# LCEDA_ProProject_2024-03-29.net
KiCad netlist of a schematic drawn in EasyEDA Pro
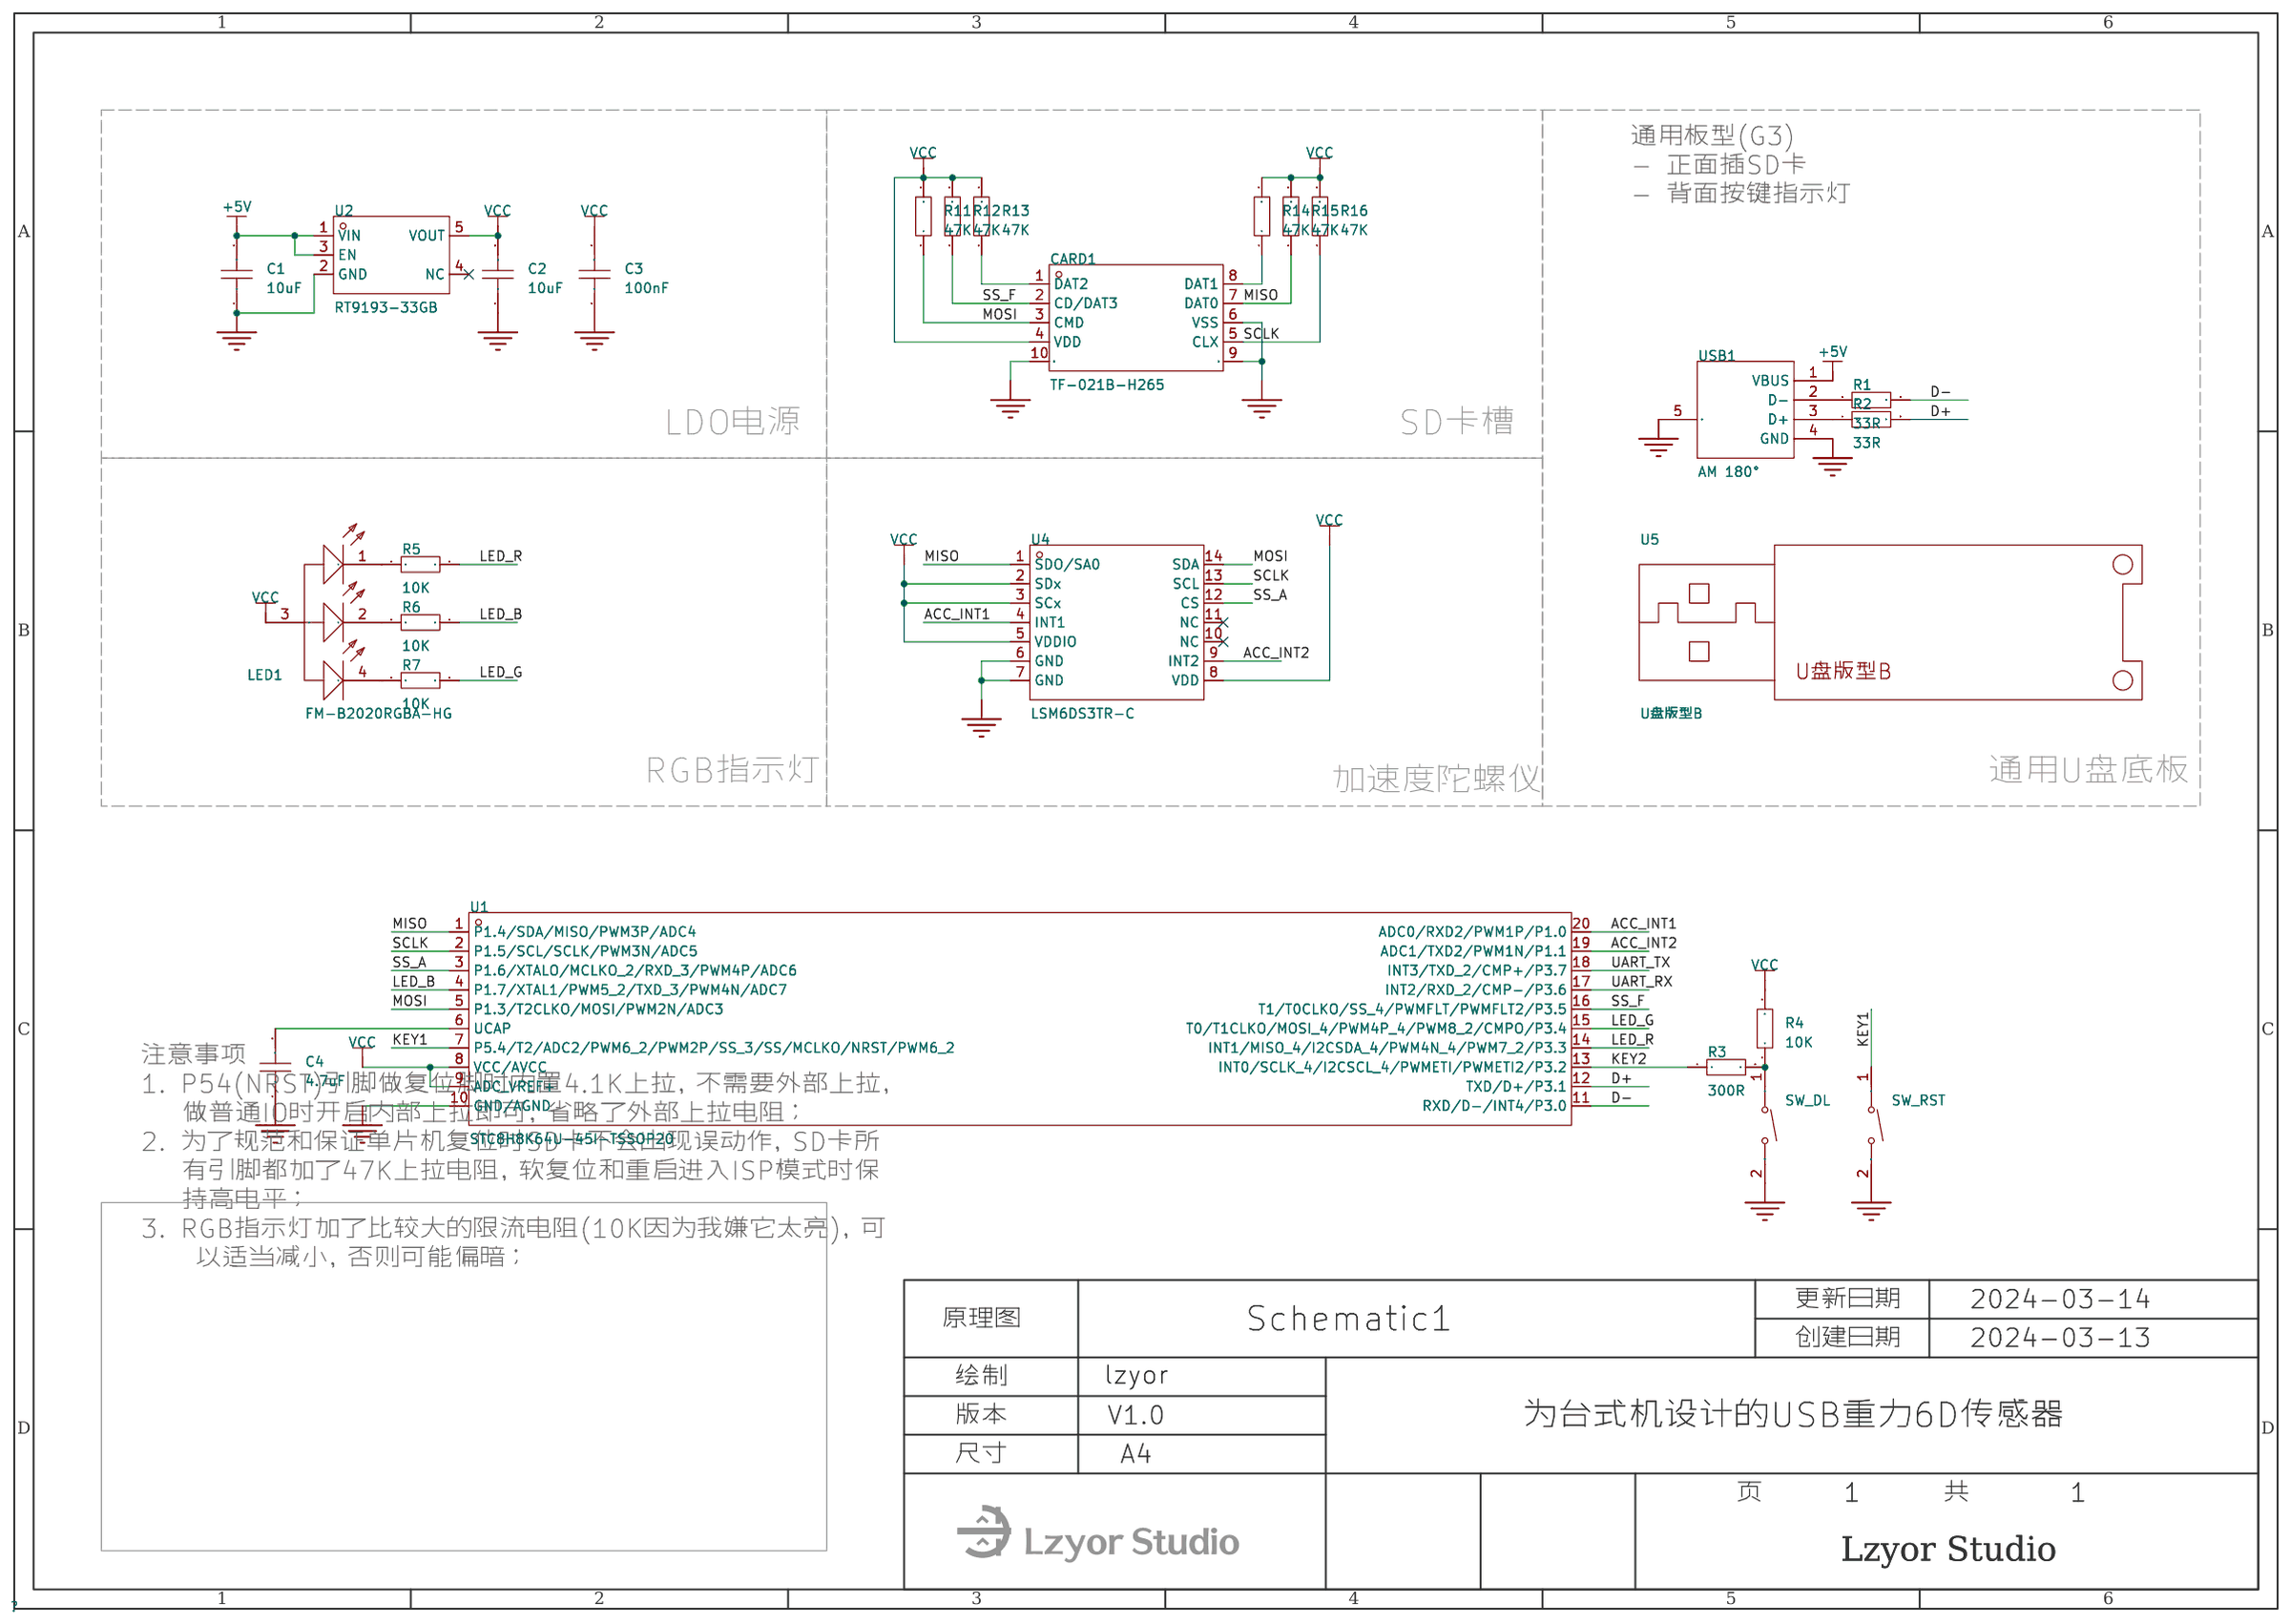
[diagram p0: schematic sheet]

(export (version "E")
  (design (tool "Eeschema 10.0.6"))
  (components
    (comp (ref "C1")
      (value "10uF")
      (footprint "easyedapro:C0603")
      (libsource (lib "easyedapro") (part "CapAcitance"))
    )
    (comp (ref "C2")
      (value "10uF")
      (footprint "easyedapro:C0603")
      (libsource (lib "easyedapro") (part "CapAcitance"))
    )
    (comp (ref "C3")
      (value "100nF")
      (footprint "easyedapro:C0603")
      (libsource (lib "easyedapro") (part "CapAcitance"))
    )
    (comp (ref "C4")
      (value "4.7uF")
      (footprint "easyedapro:C0603")
      (libsource (lib "easyedapro") (part "CapAcitance"))
    )
    (comp (ref "CARD1")
      (value "TF-021B-H265")
      (footprint "easyedapro:TF-SMD_TF-021B-H265")
      (description "卡连接方式:拔插式;卡类型:MicroSD卡(TF卡);连接器类型:卡座;本体最大高度:2.5mm;工作温度范围:-25°C~+75°C;")
      (fields (field (name "Manufacturer") "SOFNG(硕方)"))
      (libsource (lib "easyedapro") (part "TF-021B-H265"))
    )
    (comp (ref "LED1")
      (value "FM-B2020RGBA-HG")
      (footprint "easyedapro:LED-SMD_FM-B2020RGBA-HG")
      (fields (field (name "Manufacturer") "国星光电"))
      (libsource (lib "easyedapro") (part "FM-B2020RGBA-HG"))
    )
    (comp (ref "R1") (value "33R") (footprint "easyedapro:R0603") (libsource (lib "easyedapro") (part "电阻")))
    (comp (ref "R2") (value "33R") (footprint "easyedapro:R0603") (libsource (lib "easyedapro") (part "电阻")))
    (comp (ref "R3") (value "300R") (footprint "easyedapro:R0603") (libsource (lib "easyedapro") (part "电阻")))
    (comp (ref "R4") (value "10K") (footprint "easyedapro:R0603") (libsource (lib "easyedapro") (part "电阻")))
    (comp (ref "R5") (value "10K") (footprint "easyedapro:R0603") (libsource (lib "easyedapro") (part "电阻")))
    (comp (ref "R6") (value "10K") (footprint "easyedapro:R0603") (libsource (lib "easyedapro") (part "电阻")))
    (comp (ref "R7") (value "10K") (footprint "easyedapro:R0603") (libsource (lib "easyedapro") (part "电阻")))
    (comp (ref "R11") (value "47K") (footprint "easyedapro:R0603") (libsource (lib "easyedapro") (part "电阻")))
    (comp (ref "R12") (value "47K") (footprint "easyedapro:R0603") (libsource (lib "easyedapro") (part "电阻")))
    (comp (ref "R13") (value "47K") (footprint "easyedapro:R0603") (libsource (lib "easyedapro") (part "电阻")))
    (comp (ref "R14") (value "47K") (footprint "easyedapro:R0603") (libsource (lib "easyedapro") (part "电阻")))
    (comp (ref "R15") (value "47K") (footprint "easyedapro:R0603") (libsource (lib "easyedapro") (part "电阻")))
    (comp (ref "R16") (value "47K") (footprint "easyedapro:R0603") (libsource (lib "easyedapro") (part "电阻")))
    (comp (ref "SW_DL")
      (value "GT-TS024B-H0060-L3")
      (footprint "easyedapro:KEY-SMD_L3.0-W2.0-LS3.5")
      (fields (field (name "Manufacturer") "G-Switch(品赞)"))
      (libsource (lib "easyedapro") (part "GT-TS024B-H0060-L3"))
    )
    (comp (ref "SW_RST")
      (value "GT-TS024B-H0060-L3")
      (footprint "easyedapro:KEY-SMD_L3.0-W2.0-LS3.5")
      (fields (field (name "Manufacturer") "G-Switch(品赞)"))
      (libsource (lib "easyedapro") (part "GT-TS024B-H0060-L3"))
    )
    (comp (ref "U1")
      (value "STC8H8K64U-45I-TSSOP20")
      (footprint "easyedapro:TSSOP-20_L6.5-W4.4-P0.65-LS6.5-BL")
      (fields (field (name "Manufacturer") "STC(宏晶)"))
      (libsource (lib "easyedapro") (part "STC8H8K64U-45I-TSSOP20"))
    )
    (comp (ref "U2")
      (value "RT9193-33GB")
      (footprint "easyedapro:SOT-23-5_L3.0-W1.5-P0.95-LS2.8-BL")
      (fields (field (name "Manufacturer") "TECH PUBLIC(台舟)"))
      (libsource (lib "easyedapro") (part "RT9193-33GB_C19268156"))
    )
    (comp (ref "U4")
      (value "LSM6DS3TR-C")
      (footprint "easyedapro:LGA-14_L3.0-W2.5-P0.50-TL")
      (description "传感器类型:加速度计陀螺仪;")
      (fields (field (name "Manufacturer") "ST(意法半导体)"))
      (libsource (lib "easyedapro") (part "LSM6DS3TR-C"))
    )
    (comp (ref "U5")
      (value "U盘版型B")
      (footprint "easyedapro:U盘版型B")
      (libsource (lib "easyedapro") (part "U盘版型B"))
    )
    (comp (ref "USB1")
      (value "AM 180°")
      (footprint "easyedapro:USB-SMD_AM180")
      (description "连接器类型:Type-A;标准:USB 2.0;公母:公;端口数量:1;触点数量:4P;安装方式:卧贴;额定电流 - 电源:1A;工作温度范围:-40°C~+60°C;")
      (fields (field (name "Manufacturer") "SHOU HAN(首韩)"))
      (libsource (lib "easyedapro") (part "AM 180°"))
    )
  )
  (nets
    (net (code "1") (name "+5V") (class "Default")
      (node (ref "C1") (pin "2") (pinfunction "2_2") (pintype "input"))
      (node (ref "U2") (pin "1") (pinfunction "VIN_1") (pintype "unspecified"))
      (node (ref "U2") (pin "3") (pinfunction "EN_3") (pintype "unspecified"))
      (node (ref "USB1") (pin "1") (pinfunction "VBUS_1") (pintype "input"))
    )
    (net (code "2") (name "/ACC_INT1") (class "Default")
      (node (ref "U1") (pin "20") (pinfunction "ADC0/RXD2/PWM1P/P1.0_20") (pintype "unspecified"))
      (node (ref "U4") (pin "4") (pinfunction "INT1_4") (pintype "unspecified"))
    )
    (net (code "3") (name "/ACC_INT2") (class "Default")
      (node (ref "U1") (pin "19") (pinfunction "ADC1/TXD2/PWM1N/P1.1_19") (pintype "unspecified"))
      (node (ref "U4") (pin "9") (pinfunction "INT2_9") (pintype "unspecified"))
    )
    (net (code "4") (name "/D+") (class "Default")
      (node (ref "R2") (pin "2") (pinfunction "2_2") (pintype "input"))
      (node (ref "U1") (pin "12") (pinfunction "TXD/D+/P3.1_12") (pintype "unspecified"))
    )
    (net (code "5") (name "/D-") (class "Default")
      (node (ref "R1") (pin "2") (pinfunction "2_2") (pintype "input"))
      (node (ref "U1") (pin "11") (pinfunction "RXD/D-/INT4/P3.0_11") (pintype "unspecified"))
    )
    (net (code "6") (name "/KEY1") (class "Default")
      (node (ref "SW_RST") (pin "1") (pinfunction "1_1") (pintype "input"))
      (node (ref "U1") (pin "7") (pinfunction "P5.4/T2/ADC2/PWM6_2/PWM2P/SS_3/SS/MCLKO/NRST/PWM6_2_7") (pintype "unspecified"))
    )
    (net (code "7") (name "/KEY2") (class "Default")
      (node (ref "R3") (pin "1") (pinfunction "1_1") (pintype "input"))
      (node (ref "U1") (pin "13") (pinfunction "INT0/SCLK_4/I2CSCL_4/PWMETI/PWMETI2/P3.2_13") (pintype "unspecified"))
    )
    (net (code "8") (name "/LED_B") (class "Default")
      (node (ref "R6") (pin "1") (pinfunction "1_1") (pintype "input"))
      (node (ref "U1") (pin "4") (pinfunction "P1.7/XTAL1/PWM5_2/TXD_3/PWM4N/ADC7_4") (pintype "unspecified"))
    )
    (net (code "9") (name "/LED_G") (class "Default")
      (node (ref "R7") (pin "1") (pinfunction "1_1") (pintype "input"))
      (node (ref "U1") (pin "15") (pinfunction "T0/T1CLKO/MOSI_4/PWM4P_4/PWM8_2/CMPO/P3.4_15") (pintype "unspecified"))
    )
    (net (code "10") (name "/LED_R") (class "Default")
      (node (ref "R5") (pin "1") (pinfunction "1_1") (pintype "input"))
      (node (ref "U1") (pin "14") (pinfunction "INT1/MISO_4/I2CSDA_4/PWM4N_4/PWM7_2/P3.3_14") (pintype "unspecified"))
    )
    (net (code "11") (name "/MISO") (class "Default")
      (node (ref "CARD1") (pin "7") (pinfunction "DAT0_7") (pintype "unspecified"))
      (node (ref "R15") (pin "1") (pinfunction "1_1") (pintype "input"))
      (node (ref "U1") (pin "1") (pinfunction "P1.4/SDA/MISO/PWM3P/ADC4_1") (pintype "unspecified"))
      (node (ref "U4") (pin "1") (pinfunction "SDO/SA0_1") (pintype "unspecified"))
    )
    (net (code "12") (name "/MOSI") (class "Default")
      (node (ref "CARD1") (pin "3") (pinfunction "CMD_3") (pintype "unspecified"))
      (node (ref "R11") (pin "1") (pinfunction "1_1") (pintype "input"))
      (node (ref "U1") (pin "5") (pinfunction "P1.3/T2CLKO/MOSI/PWM2N/ADC3_5") (pintype "unspecified"))
      (node (ref "U4") (pin "14") (pinfunction "SDA_14") (pintype "unspecified"))
    )
    (net (code "13") (name "/SCLK") (class "Default")
      (node (ref "CARD1") (pin "5") (pinfunction "CLX_5") (pintype "unspecified"))
      (node (ref "R16") (pin "1") (pinfunction "1_1") (pintype "input"))
      (node (ref "U1") (pin "2") (pinfunction "P1.5/SCL/SCLK/PWM3N/ADC5_2") (pintype "unspecified"))
      (node (ref "U4") (pin "13") (pinfunction "SCL_13") (pintype "unspecified"))
    )
    (net (code "14") (name "/SS_A") (class "Default")
      (node (ref "U1") (pin "3") (pinfunction "P1.6/XTALO/MCLKO_2/RXD_3/PWM4P/ADC6_3") (pintype "unspecified"))
      (node (ref "U4") (pin "12") (pinfunction "CS_12") (pintype "unspecified"))
    )
    (net (code "15") (name "/SS_F") (class "Default")
      (node (ref "CARD1") (pin "2") (pinfunction "CD/DAT3_2") (pintype "unspecified"))
      (node (ref "R12") (pin "1") (pinfunction "1_1") (pintype "input"))
      (node (ref "U1") (pin "16") (pinfunction "T1/T0CLKO/SS_4/PWMFLT/PWMFLT2/P3.5_16") (pintype "unspecified"))
    )
    (net (code "16") (name "/UART_RX") (class "Default")
      (node (ref "U1") (pin "17") (pinfunction "INT2/RXD_2/CMP-/P3.6_17") (pintype "unspecified"))
    )
    (net (code "17") (name "/UART_TX") (class "Default")
      (node (ref "U1") (pin "18") (pinfunction "INT3/TXD_2/CMP+/P3.7_18") (pintype "unspecified"))
    )
    (net (code "18") (name "GND") (class "Default")
      (node (ref "C1") (pin "1") (pinfunction "1_1") (pintype "input"))
      (node (ref "C2") (pin "1") (pinfunction "1_1") (pintype "input"))
      (node (ref "C3") (pin "1") (pinfunction "1_1") (pintype "input"))
      (node (ref "C4") (pin "1") (pinfunction "1_1") (pintype "input"))
      (node (ref "CARD1") (pin "10") (pinfunction "10_10") (pintype "unspecified"))
      (node (ref "CARD1") (pin "6") (pinfunction "VSS_6") (pintype "unspecified"))
      (node (ref "CARD1") (pin "9") (pinfunction "9_9") (pintype "unspecified"))
      (node (ref "SW_DL") (pin "2") (pinfunction "2_2") (pintype "input"))
      (node (ref "SW_RST") (pin "2") (pinfunction "2_2") (pintype "input"))
      (node (ref "U1") (pin "10") (pinfunction "GND/AGND_10") (pintype "unspecified"))
      (node (ref "U2") (pin "2") (pinfunction "GND_2") (pintype "unspecified"))
      (node (ref "U4") (pin "6") (pinfunction "GND_6") (pintype "unspecified"))
      (node (ref "U4") (pin "7") (pinfunction "GND_7") (pintype "unspecified"))
      (node (ref "USB1") (pin "4") (pinfunction "GND_4") (pintype "input"))
      (node (ref "USB1") (pin "5") (pinfunction "EH_5") (pintype "input"))
    )
    (net (code "19") (name "Net-(CARD1-DAT1)") (class "Default")
      (node (ref "CARD1") (pin "8") (pinfunction "DAT1_8") (pintype "unspecified"))
      (node (ref "R14") (pin "1") (pinfunction "1_1") (pintype "input"))
    )
    (net (code "20") (name "Net-(CARD1-DAT2)") (class "Default")
      (node (ref "CARD1") (pin "1") (pinfunction "DAT2_1") (pintype "unspecified"))
      (node (ref "R13") (pin "1") (pinfunction "1_1") (pintype "input"))
    )
    (net (code "21") (name "Net-(LED1-K-Pad1)") (class "Default")
      (node (ref "LED1") (pin "1") (pinfunction "K_1") (pintype "unspecified"))
      (node (ref "R5") (pin "2") (pinfunction "2_2") (pintype "input"))
    )
    (net (code "22") (name "Net-(LED1-K-Pad2)") (class "Default")
      (node (ref "LED1") (pin "2") (pinfunction "K_2") (pintype "unspecified"))
      (node (ref "R6") (pin "2") (pinfunction "2_2") (pintype "input"))
    )
    (net (code "23") (name "Net-(LED1-K-Pad4)") (class "Default")
      (node (ref "LED1") (pin "4") (pinfunction "K_4") (pintype "unspecified"))
      (node (ref "R7") (pin "2") (pinfunction "2_2") (pintype "input"))
    )
    (net (code "24") (name "Net-(R3-Pad2)") (class "Default")
      (node (ref "R3") (pin "2") (pinfunction "2_2") (pintype "input"))
      (node (ref "R4") (pin "1") (pinfunction "1_1") (pintype "input"))
      (node (ref "SW_DL") (pin "1") (pinfunction "1_1") (pintype "input"))
    )
    (net (code "25") (name "Net-(U1-UCAP)") (class "Default")
      (node (ref "C4") (pin "2") (pinfunction "2_2") (pintype "input"))
      (node (ref "U1") (pin "6") (pinfunction "UCAP_6") (pintype "unspecified"))
    )
    (net (code "26") (name "Net-(USB1-D+)") (class "Default")
      (node (ref "R2") (pin "1") (pinfunction "1_1") (pintype "input"))
      (node (ref "USB1") (pin "3") (pinfunction "D+_3") (pintype "input"))
    )
    (net (code "27") (name "Net-(USB1-D-)") (class "Default")
      (node (ref "R1") (pin "1") (pinfunction "1_1") (pintype "input"))
      (node (ref "USB1") (pin "2") (pinfunction "D-_2") (pintype "input"))
    )
    (net (code "28") (name "VCC") (class "Default")
      (node (ref "C2") (pin "2") (pinfunction "2_2") (pintype "input"))
      (node (ref "C3") (pin "2") (pinfunction "2_2") (pintype "input"))
      (node (ref "CARD1") (pin "4") (pinfunction "VDD_4") (pintype "unspecified"))
      (node (ref "LED1") (pin "3") (pinfunction "A_3") (pintype "unspecified"))
      (node (ref "R11") (pin "2") (pinfunction "2_2") (pintype "input"))
      (node (ref "R12") (pin "2") (pinfunction "2_2") (pintype "input"))
      (node (ref "R13") (pin "2") (pinfunction "2_2") (pintype "input"))
      (node (ref "R14") (pin "2") (pinfunction "2_2") (pintype "input"))
      (node (ref "R15") (pin "2") (pinfunction "2_2") (pintype "input"))
      (node (ref "R16") (pin "2") (pinfunction "2_2") (pintype "input"))
      (node (ref "R4") (pin "2") (pinfunction "2_2") (pintype "input"))
      (node (ref "U1") (pin "8") (pinfunction "VCC/AVCC_8") (pintype "unspecified"))
      (node (ref "U1") (pin "9") (pinfunction "ADC_VREF+_9") (pintype "unspecified"))
      (node (ref "U2") (pin "5") (pinfunction "VOUT_5") (pintype "unspecified"))
      (node (ref "U4") (pin "2") (pinfunction "SDx_2") (pintype "unspecified"))
      (node (ref "U4") (pin "3") (pinfunction "SCx_3") (pintype "unspecified"))
      (node (ref "U4") (pin "5") (pinfunction "VDDIO_5") (pintype "unspecified"))
      (node (ref "U4") (pin "8") (pinfunction "VDD_8") (pintype "unspecified"))
    )
    (net (code "29") (name "unconnected-(U2-NC-Pad4)") (class "Default")
      (node (ref "U2") (pin "4") (pinfunction "NC_4") (pintype "unspecified+no_connect"))
    )
    (net (code "30") (name "unconnected-(U4-NC-Pad10)") (class "Default")
      (node (ref "U4") (pin "10") (pinfunction "NC_10") (pintype "unspecified+no_connect"))
    )
    (net (code "31") (name "unconnected-(U4-NC-Pad11)") (class "Default")
      (node (ref "U4") (pin "11") (pinfunction "NC_11") (pintype "unspecified+no_connect"))
    )
  )
)
